# ATM90E26_Breakout.net
KiCad netlist of a schematic drawn in EAGLE
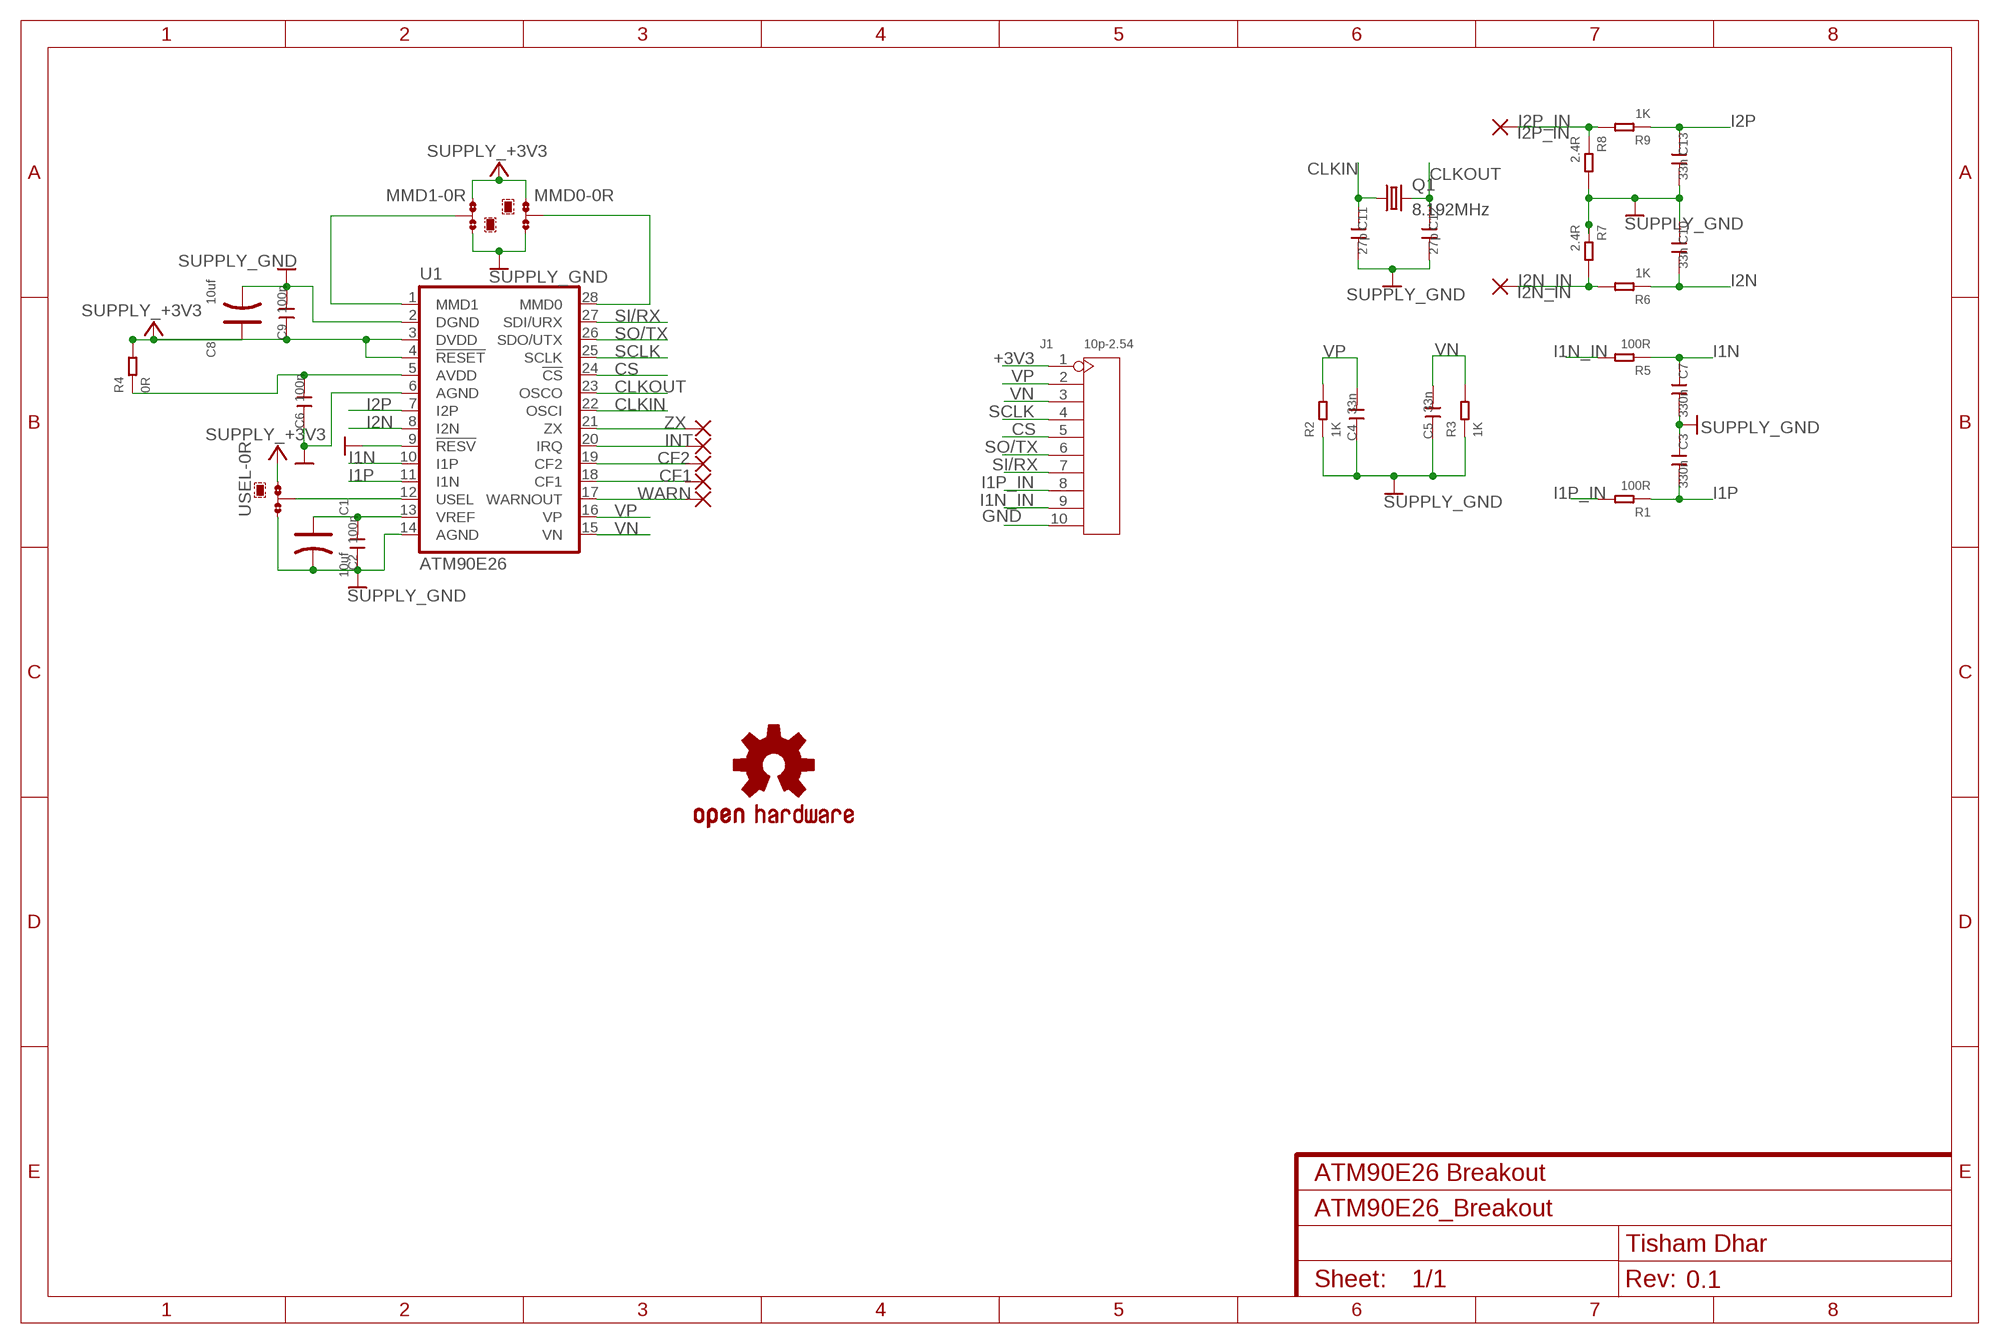
[diagram p0: schematic, sheet 1]

(export (version "E")
  (design (tool "Eeschema 10.0.6"))
  (components
    (comp (ref "C1")
      (value "10uf")
      (footprint "eagle-import:AVX-A")
      (fields (field (name "MPN") "TAJA226*010#NJ"))
      (libsource (lib "eagle-import") (part "TANTALUM-SMD-22UF-10V(AVX-A)"))
    )
    (comp (ref "C2")
      (value "100n")
      (footprint "eagle-import:C0603")
      (libsource (lib "eagle-import") (part "C-0603"))
    )
    (comp (ref "C3")
      (value "330n")
      (footprint "eagle-import:C0603")
      (libsource (lib "eagle-import") (part "C-0603"))
    )
    (comp (ref "C4")
      (value "33n")
      (footprint "eagle-import:C0603")
      (libsource (lib "eagle-import") (part "C-0603"))
    )
    (comp (ref "C5")
      (value "33n")
      (footprint "eagle-import:C0603")
      (libsource (lib "eagle-import") (part "C-0603"))
    )
    (comp (ref "C6")
      (value "100n")
      (footprint "eagle-import:C0603")
      (libsource (lib "eagle-import") (part "C-0603"))
    )
    (comp (ref "C7")
      (value "330n")
      (footprint "eagle-import:C0603")
      (libsource (lib "eagle-import") (part "C-0603"))
    )
    (comp (ref "C8")
      (value "10uf")
      (footprint "eagle-import:AVX-A")
      (fields (field (name "MPN") "TAJA226*010#NJ"))
      (libsource (lib "eagle-import") (part "TANTALUM-SMD-22UF-10V(AVX-A)"))
    )
    (comp (ref "C9")
      (value "100n")
      (footprint "eagle-import:C0603")
      (libsource (lib "eagle-import") (part "C-0603"))
    )
    (comp (ref "C10")
      (value "33n")
      (footprint "eagle-import:C0603")
      (libsource (lib "eagle-import") (part "C-0603"))
    )
    (comp (ref "C11")
      (value "27p")
      (footprint "eagle-import:C0603")
      (libsource (lib "eagle-import") (part "C-0603"))
    )
    (comp (ref "C12")
      (value "27p")
      (footprint "eagle-import:C0603")
      (libsource (lib "eagle-import") (part "C-0603"))
    )
    (comp (ref "C13")
      (value "33n")
      (footprint "eagle-import:C0603")
      (libsource (lib "eagle-import") (part "C-0603"))
    )
    (comp (ref "CF1")
      (value "WIREPADSMD1,27-254")
      (footprint "eagle-import:SMD1,27-2,54")
      (libsource (lib "eagle-import") (part "WIREPADSMD1,27-254"))
    )
    (comp (ref "CF2")
      (value "WIREPADSMD1,27-254")
      (footprint "eagle-import:SMD1,27-2,54")
      (libsource (lib "eagle-import") (part "WIREPADSMD1,27-254"))
    )
    (comp (ref "I2N_IN")
      (value "WIREPADSMD1,27-254")
      (footprint "eagle-import:SMD1,27-2,54")
      (libsource (lib "eagle-import") (part "WIREPADSMD1,27-254"))
    )
    (comp (ref "I2P_IN")
      (value "WIREPADSMD1,27-254")
      (footprint "eagle-import:SMD1,27-2,54")
      (libsource (lib "eagle-import") (part "WIREPADSMD1,27-254"))
    )
    (comp (ref "INT")
      (value "WIREPADSMD1,27-254")
      (footprint "eagle-import:SMD1,27-2,54")
      (libsource (lib "eagle-import") (part "WIREPADSMD1,27-254"))
    )
    (comp (ref "J1")
      (value "10p-2.54")
      (footprint "eagle-import:H10-2.54")
      (fields (field (name "MPN") "P125-1110A0BS116AX"))
      (libsource (lib "eagle-import") (part "DIP-BLACK-MALE-HEADER-VERT(10P-2.54)"))
    )
    (comp (ref "LOGO1")
      (value "OSHW-LOGOM")
      (footprint "eagle-import:OSHW-LOGO-M")
      (libsource (lib "eagle-import") (part "OSHW-LOGOM"))
    )
    (comp (ref "MMD0")
      (value "0R-JUMPA")
      (footprint "eagle-import:A0R-JMP")
      (libsource (lib "eagle-import") (part "0R-JUMPA"))
    )
    (comp (ref "MMD1")
      (value "0R-JUMPA")
      (footprint "eagle-import:A0R-JMP")
      (libsource (lib "eagle-import") (part "0R-JUMPA"))
    )
    (comp (ref "Q1")
      (value "8.192MHz")
      (footprint "eagle-import:HC49UP")
      (libsource (lib "eagle-import") (part "CRYSTALHC49UP"))
    )
    (comp (ref "R1")
      (value "100R")
      (footprint "eagle-import:R0603")
      (fields (field (name "MPN") "RC0603FR-071KL"))
      (libsource (lib "eagle-import") (part "SMD-RES-1K(0603)"))
    )
    (comp (ref "R2")
      (value "1K")
      (footprint "eagle-import:R0603")
      (fields (field (name "MPN") "RC0603FR-071KL"))
      (libsource (lib "eagle-import") (part "SMD-RES-1K(0603)"))
    )
    (comp (ref "R3")
      (value "1K")
      (footprint "eagle-import:R0603")
      (fields (field (name "MPN") "RC0603FR-071KL"))
      (libsource (lib "eagle-import") (part "SMD-RES-1K(0603)"))
    )
    (comp (ref "R4")
      (value "0R")
      (footprint "eagle-import:R0603")
      (fields (field (name "MPN") "RC0603JR-070RL"))
      (libsource (lib "eagle-import") (part "SMD-RES-0R(0603)"))
    )
    (comp (ref "R5")
      (value "100R")
      (footprint "eagle-import:R0603")
      (fields (field (name "MPN") "RC0603FR-071KL"))
      (libsource (lib "eagle-import") (part "SMD-RES-1K(0603)"))
    )
    (comp (ref "R6")
      (value "1K")
      (footprint "eagle-import:R0603")
      (fields (field (name "MPN") "RC0603FR-071KL"))
      (libsource (lib "eagle-import") (part "SMD-RES-1K(0603)"))
    )
    (comp (ref "R7")
      (value "2.4R")
      (footprint "eagle-import:R0603")
      (fields (field (name "MPN") "RC0603FR-071KL"))
      (libsource (lib "eagle-import") (part "SMD-RES-1K(0603)"))
    )
    (comp (ref "R8")
      (value "2.4R")
      (footprint "eagle-import:R0603")
      (fields (field (name "MPN") "RC0603FR-071KL"))
      (libsource (lib "eagle-import") (part "SMD-RES-1K(0603)"))
    )
    (comp (ref "R9")
      (value "1K")
      (footprint "eagle-import:R0603")
      (fields (field (name "MPN") "RC0603FR-071KL"))
      (libsource (lib "eagle-import") (part "SMD-RES-1K(0603)"))
    )
    (comp (ref "U1")
      (value "ATM90E26")
      (footprint "eagle-import:SSOP-28")
      (libsource (lib "eagle-import") (part "ATM90E26"))
    )
    (comp (ref "USEL")
      (value "0R-JUMPA")
      (footprint "eagle-import:A0R-JMP")
      (libsource (lib "eagle-import") (part "0R-JUMPA"))
    )
    (comp (ref "WARN")
      (value "WIREPADSMD1,27-254")
      (footprint "eagle-import:SMD1,27-2,54")
      (libsource (lib "eagle-import") (part "WIREPADSMD1,27-254"))
    )
    (comp (ref "ZX")
      (value "WIREPADSMD1,27-254")
      (footprint "eagle-import:SMD1,27-2,54")
      (libsource (lib "eagle-import") (part "WIREPADSMD1,27-254"))
    )
  )
  (nets
    (net (code "1") (name "/CLKIN") (class "Default")
      (node (ref "C11") (pin "1") (pinfunction "1_1") (pintype "passive"))
      (node (ref "Q1") (pin "1") (pinfunction "1_1") (pintype "passive"))
      (node (ref "U1") (pin "22") (pinfunction "OSCI_22") (pintype "input"))
    )
    (net (code "2") (name "/CLKOUT") (class "Default")
      (node (ref "C12") (pin "1") (pinfunction "1_1") (pintype "passive"))
      (node (ref "Q1") (pin "2") (pinfunction "2_2") (pintype "passive"))
      (node (ref "U1") (pin "23") (pinfunction "OSCO_23") (pintype "output"))
    )
    (net (code "3") (name "/CS") (class "Default")
      (node (ref "J1") (pin "5") (pinfunction "5_5") (pintype "bidirectional"))
      (node (ref "U1") (pin "24") (pinfunction "~{CS}_24") (pintype "input"))
    )
    (net (code "4") (name "/I1N") (class "Default")
      (node (ref "C7") (pin "1") (pinfunction "1_1") (pintype "passive"))
      (node (ref "R5") (pin "1") (pinfunction "1_1") (pintype "passive"))
      (node (ref "U1") (pin "10") (pinfunction "I1P_10") (pintype "input"))
    )
    (net (code "5") (name "/I1N_IN") (class "Default")
      (node (ref "J1") (pin "9") (pinfunction "9_9") (pintype "bidirectional"))
      (node (ref "R5") (pin "2") (pinfunction "2_2") (pintype "passive"))
    )
    (net (code "6") (name "/I1P") (class "Default")
      (node (ref "C3") (pin "2") (pinfunction "2_2") (pintype "passive"))
      (node (ref "R1") (pin "1") (pinfunction "1_1") (pintype "passive"))
      (node (ref "U1") (pin "11") (pinfunction "I1N_11") (pintype "input"))
    )
    (net (code "7") (name "/I1P_IN") (class "Default")
      (node (ref "J1") (pin "8") (pinfunction "8_8") (pintype "bidirectional"))
      (node (ref "R1") (pin "2") (pinfunction "2_2") (pintype "passive"))
    )
    (net (code "8") (name "/I2N") (class "Default")
      (node (ref "C10") (pin "2") (pinfunction "2_2") (pintype "passive"))
      (node (ref "R6") (pin "1") (pinfunction "1_1") (pintype "passive"))
      (node (ref "U1") (pin "8") (pinfunction "I2N_8") (pintype "input"))
    )
    (net (code "9") (name "/I2N_IN") (class "Default")
      (node (ref "I2N_IN") (pin "1") (pinfunction "P_1") (pintype "passive"))
      (node (ref "R6") (pin "2") (pinfunction "2_2") (pintype "passive"))
      (node (ref "R7") (pin "2") (pinfunction "2_2") (pintype "passive"))
    )
    (net (code "10") (name "/I2P") (class "Default")
      (node (ref "C13") (pin "1") (pinfunction "1_1") (pintype "passive"))
      (node (ref "R9") (pin "1") (pinfunction "1_1") (pintype "passive"))
      (node (ref "U1") (pin "7") (pinfunction "I2P_7") (pintype "input"))
    )
    (net (code "11") (name "/I2P_IN") (class "Default")
      (node (ref "I2P_IN") (pin "1") (pinfunction "P_1") (pintype "passive"))
      (node (ref "R8") (pin "1") (pinfunction "1_1") (pintype "passive"))
      (node (ref "R9") (pin "2") (pinfunction "2_2") (pintype "passive"))
    )
    (net (code "12") (name "/SCLK") (class "Default")
      (node (ref "J1") (pin "4") (pinfunction "4_4") (pintype "bidirectional"))
      (node (ref "U1") (pin "25") (pinfunction "SCLK_25") (pintype "input"))
    )
    (net (code "13") (name "/SI{slash}RX") (class "Default")
      (node (ref "J1") (pin "7") (pinfunction "7_7") (pintype "bidirectional"))
      (node (ref "U1") (pin "27") (pinfunction "SDI/URX_27") (pintype "input"))
    )
    (net (code "14") (name "/SO{slash}TX") (class "Default")
      (node (ref "J1") (pin "6") (pinfunction "6_6") (pintype "bidirectional"))
      (node (ref "U1") (pin "26") (pinfunction "SDO/UTX_26") (pintype "output"))
    )
    (net (code "15") (name "/VN") (class "Default")
      (node (ref "C5") (pin "2") (pinfunction "2_2") (pintype "passive"))
      (node (ref "J1") (pin "3") (pinfunction "3_3") (pintype "bidirectional"))
      (node (ref "R3") (pin "2") (pinfunction "2_2") (pintype "passive"))
      (node (ref "U1") (pin "15") (pinfunction "VN_15") (pintype "input"))
    )
    (net (code "16") (name "/VP") (class "Default")
      (node (ref "C4") (pin "2") (pinfunction "2_2") (pintype "passive"))
      (node (ref "J1") (pin "2") (pinfunction "2_2") (pintype "bidirectional"))
      (node (ref "R2") (pin "2") (pinfunction "2_2") (pintype "passive"))
      (node (ref "U1") (pin "16") (pinfunction "VP_16") (pintype "input"))
    )
    (net (code "17") (name "Net-(CF1-P)") (class "Default")
      (node (ref "CF1") (pin "1") (pinfunction "P_1") (pintype "passive"))
      (node (ref "U1") (pin "18") (pinfunction "CF1_18") (pintype "output"))
    )
    (net (code "18") (name "Net-(CF2-P)") (class "Default")
      (node (ref "CF2") (pin "1") (pinfunction "P_1") (pintype "passive"))
      (node (ref "U1") (pin "19") (pinfunction "CF2_19") (pintype "output"))
    )
    (net (code "19") (name "Net-(INT-P)") (class "Default")
      (node (ref "INT") (pin "1") (pinfunction "P_1") (pintype "passive"))
      (node (ref "U1") (pin "20") (pinfunction "IRQ_20") (pintype "output"))
    )
    (net (code "20") (name "Net-(U1-AVDD)") (class "Default")
      (node (ref "C6") (pin "2") (pinfunction "2_2") (pintype "passive"))
      (node (ref "R4") (pin "1") (pinfunction "1_1") (pintype "passive"))
      (node (ref "U1") (pin "5") (pinfunction "AVDD_5") (pintype "power_in"))
    )
    (net (code "21") (name "Net-(U1-MMD0)") (class "Default")
      (node (ref "MMD0") (pin "2") (pinfunction "2_2") (pintype "passive"))
      (node (ref "U1") (pin "28") (pinfunction "MMD0_28") (pintype "input"))
    )
    (net (code "22") (name "Net-(U1-MMD1)") (class "Default")
      (node (ref "MMD1") (pin "2") (pinfunction "2_2") (pintype "passive"))
      (node (ref "U1") (pin "1") (pinfunction "MMD1_1") (pintype "input"))
    )
    (net (code "23") (name "Net-(U1-USEL)") (class "Default")
      (node (ref "U1") (pin "12") (pinfunction "USEL_12") (pintype "input"))
      (node (ref "USEL") (pin "2") (pinfunction "2_2") (pintype "passive"))
    )
    (net (code "24") (name "Net-(U1-VREF)") (class "Default")
      (node (ref "C1") (pin "+") (pinfunction "+_+") (pintype "passive"))
      (node (ref "C2") (pin "2") (pinfunction "2_2") (pintype "passive"))
      (node (ref "U1") (pin "13") (pinfunction "VREF_13") (pintype "power_in"))
    )
    (net (code "25") (name "Net-(U1-WARNOUT)") (class "Default")
      (node (ref "U1") (pin "17") (pinfunction "WARNOUT_17") (pintype "output"))
      (node (ref "WARN") (pin "1") (pinfunction "P_1") (pintype "passive"))
    )
    (net (code "26") (name "Net-(U1-ZX)") (class "Default")
      (node (ref "U1") (pin "21") (pinfunction "ZX_21") (pintype "bidirectional"))
      (node (ref "ZX") (pin "1") (pinfunction "P_1") (pintype "passive"))
    )
    (net (code "27") (name "SUPPLY_+3V3") (class "Default")
      (node (ref "C8") (pin "+") (pinfunction "+_+") (pintype "passive"))
      (node (ref "C9") (pin "1") (pinfunction "1_1") (pintype "passive"))
      (node (ref "J1") (pin "1") (pinfunction "1_1") (pintype "bidirectional"))
      (node (ref "MMD0") (pin "1") (pinfunction "1_1") (pintype "passive"))
      (node (ref "MMD1") (pin "3") (pinfunction "3_3") (pintype "passive"))
      (node (ref "R4") (pin "2") (pinfunction "2_2") (pintype "passive"))
      (node (ref "U1") (pin "3") (pinfunction "DVDD_3") (pintype "power_in"))
      (node (ref "U1") (pin "4") (pinfunction "~{RESET}_4") (pintype "input"))
      (node (ref "USEL") (pin "1") (pinfunction "1_1") (pintype "passive"))
    )
    (net (code "28") (name "SUPPLY_GND") (class "Default")
      (node (ref "C1") (pin "-") (pinfunction "-_-") (pintype "passive"))
      (node (ref "C10") (pin "1") (pinfunction "1_1") (pintype "passive"))
      (node (ref "C11") (pin "2") (pinfunction "2_2") (pintype "passive"))
      (node (ref "C12") (pin "2") (pinfunction "2_2") (pintype "passive"))
      (node (ref "C13") (pin "2") (pinfunction "2_2") (pintype "passive"))
      (node (ref "C2") (pin "1") (pinfunction "1_1") (pintype "passive"))
      (node (ref "C3") (pin "1") (pinfunction "1_1") (pintype "passive"))
      (node (ref "C4") (pin "1") (pinfunction "1_1") (pintype "passive"))
      (node (ref "C5") (pin "1") (pinfunction "1_1") (pintype "passive"))
      (node (ref "C6") (pin "1") (pinfunction "1_1") (pintype "passive"))
      (node (ref "C7") (pin "2") (pinfunction "2_2") (pintype "passive"))
      (node (ref "C8") (pin "-") (pinfunction "-_-") (pintype "passive"))
      (node (ref "C9") (pin "2") (pinfunction "2_2") (pintype "passive"))
      (node (ref "J1") (pin "10") (pinfunction "10_10") (pintype "bidirectional"))
      (node (ref "MMD0") (pin "3") (pinfunction "3_3") (pintype "passive"))
      (node (ref "MMD1") (pin "1") (pinfunction "1_1") (pintype "passive"))
      (node (ref "R2") (pin "1") (pinfunction "1_1") (pintype "passive"))
      (node (ref "R3") (pin "1") (pinfunction "1_1") (pintype "passive"))
      (node (ref "R7") (pin "1") (pinfunction "1_1") (pintype "passive"))
      (node (ref "R8") (pin "2") (pinfunction "2_2") (pintype "passive"))
      (node (ref "U1") (pin "14") (pinfunction "AGND_14") (pintype "power_in"))
      (node (ref "U1") (pin "2") (pinfunction "DGND_2") (pintype "power_in"))
      (node (ref "U1") (pin "6") (pinfunction "AGND_6") (pintype "power_in"))
      (node (ref "U1") (pin "9") (pinfunction "~{RESV}_9") (pintype "input"))
      (node (ref "USEL") (pin "3") (pinfunction "3_3") (pintype "passive"))
    )
  )
)
